# Sheet1.net
KiCad netlist of a schematic drawn in Altium Designer
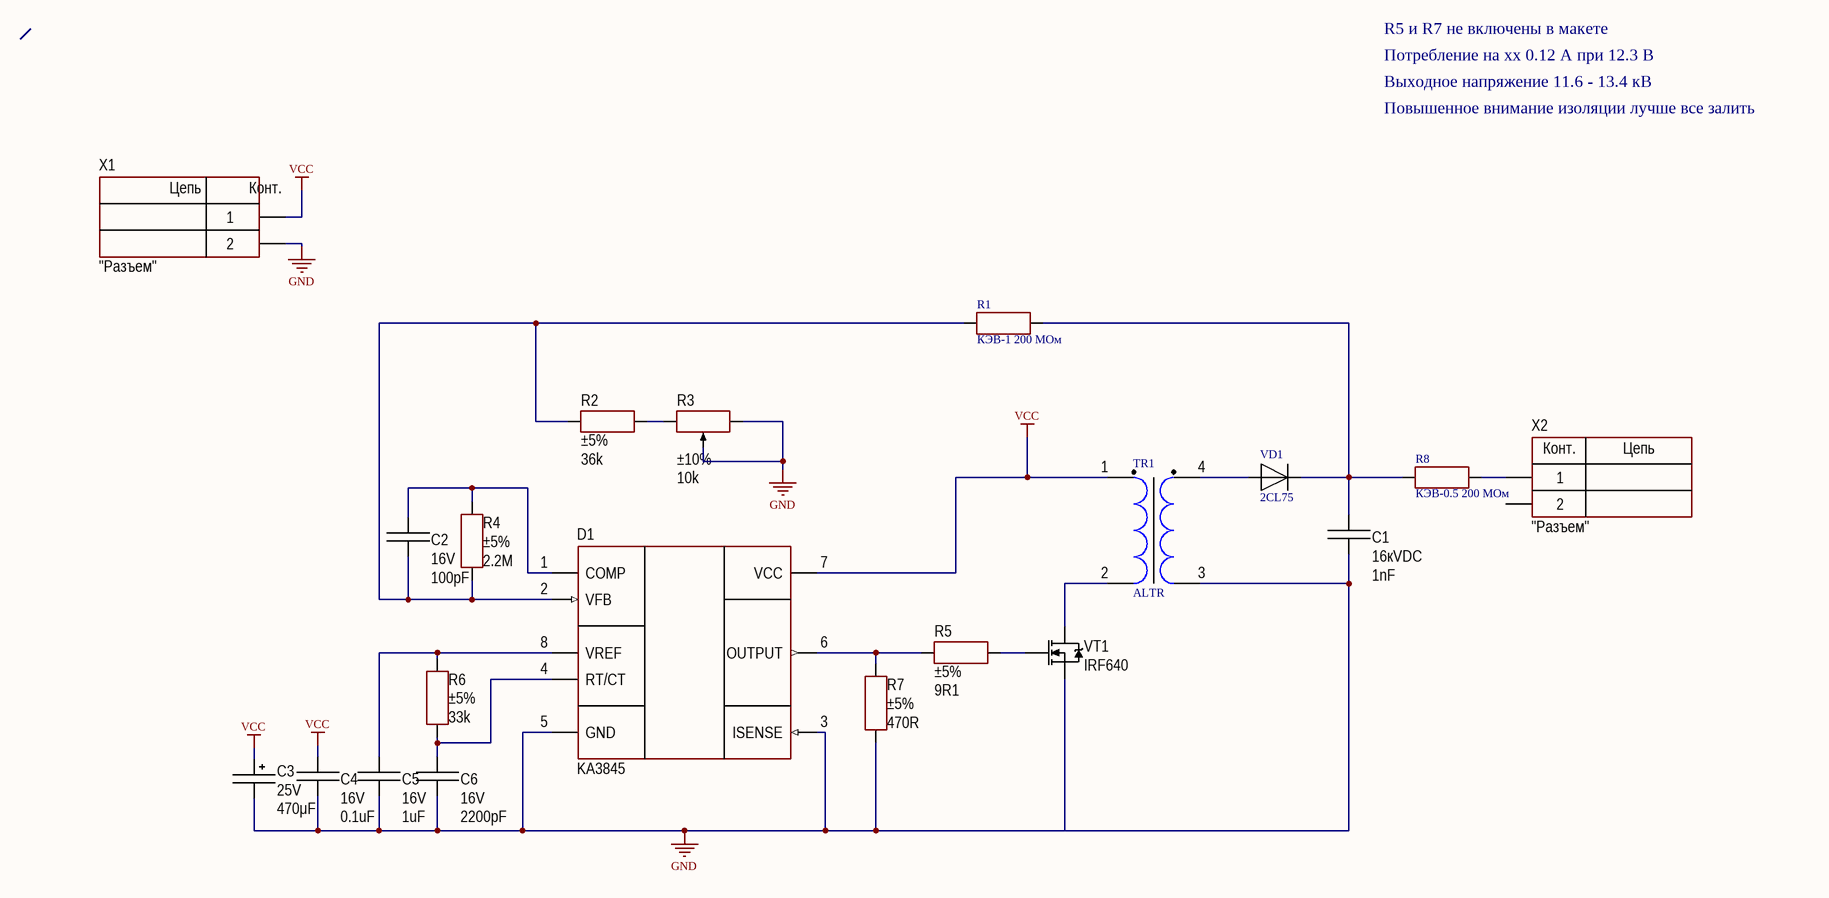
[diagram p0: Sheet1.SchDoc]

(export (version "E")
  (design (tool "Eeschema 10.0.6"))
  (components
    (comp (ref "C1")
      (value "1nF")
      (footprint "HV CAP")
      (fields
        (field (name "MANUFACTURER") "Epcos")
        (field (name "PARTNUMBER") "B32774D4106K000")
        (field (name "VALUEMANUFACTURERPARTNUMBER") "Film capacitor, 1nF, 16кVDC, ±10%, 10.9mOhm, 31.5x15 mm, -40...+105°C")
        (field (name "VOLTAGE") "16кVDC")
      )
      (libsource (lib "capacitor") (part "Film"))
    )
    (comp (ref "C2")
      (value "100pF")
      (footprint "CAP: 0805")
      (fields
        (field (name "MANUFACTURER") "Yageo")
        (field (name "PARTNUMBER") "CC0805KRX7R7BB104")
        (field (name "VALUEMANUFACTURERPARTNUMBER") "Ceramic capacitor, 100pF, X7R, ±10%, 16V, 0805, -55...+125°C")
        (field (name "VOLTAGE") "16V")
      )
      (libsource (lib "capacitor") (part "Ceramic_0805"))
    )
    (comp (ref "C3")
      (value "470μF")
      (footprint "CAP: D10C5H12.5")
      (fields
        (field (name "MANUFACTURER") "Wurth")
        (field (name "PARTNUMBER") "860080475013")
        (field (name "VALUEMANUFACTURERPARTNUMBER") "Aluminium capacitor, 470μF, 25V, ±20%, 54mOhm, 14x10x5 mm, -55...+105°C")
        (field (name "VOLTAGE") "25V")
      )
      (libsource (lib "capacitor") (part "Aluminium"))
    )
    (comp (ref "C4")
      (value "0.1uF")
      (footprint "CAP: 0805")
      (fields
        (field (name "MANUFACTURER") "Yageo")
        (field (name "PARTNUMBER") "CC0805KRX7R7BB104")
        (field (name "VALUEMANUFACTURERPARTNUMBER") "Ceramic capacitor, 0.1uF, X7R, ±10%, 16V, 0805, -55...+125°C")
        (field (name "VOLTAGE") "16V")
      )
      (libsource (lib "capacitor") (part "Ceramic_0805"))
    )
    (comp (ref "C5")
      (value "1uF")
      (footprint "CAP: 0805")
      (fields
        (field (name "MANUFACTURER") "Yageo")
        (field (name "PARTNUMBER") "CC0805KRX7R7BB104")
        (field (name "VALUEMANUFACTURERPARTNUMBER") "Ceramic capacitor, 1uF, X7R, ±10%, 16V, 0805, -55...+125°C")
        (field (name "VOLTAGE") "16V")
      )
      (libsource (lib "capacitor") (part "Ceramic_0805"))
    )
    (comp (ref "C6")
      (value "2200pF")
      (footprint "CAP: 0805")
      (fields
        (field (name "MANUFACTURER") "Yageo")
        (field (name "PARTNUMBER") "CC0805KRX7R7BB104")
        (field (name "VALUEMANUFACTURERPARTNUMBER") "Ceramic capacitor, 2200pF, X7R, ±10%, 16V, 0805, -55...+125°C")
        (field (name "VOLTAGE") "16V")
      )
      (libsource (lib "capacitor") (part "Ceramic_0805"))
    )
    (comp (ref "D1")
      (value "~")
      (footprint "8-SOIC")
      (description "PWM controller")
      (fields
        (field (name "MANUFACTURER") "ON Semiconductor")
        (field (name "VALUEMANUFACTURERPARTNUMBER") "PWM controller, supply 10...30V, 500kHz, External switch, -40...+105°C, 8-SOIC")
        (field (name "PARTNUMBER") "KA3845")
      )
      (libsource (lib "ic-power-supply") (part "UC3842BVD1R2G"))
    )
    (comp (ref "R1")
      (value "КЭВ-1 200 МОм")
      (footprint "КЭВ-1 case")
      (libsource (lib "resistor") (part "HV RESISTOR КЭВ-1"))
    )
    (comp (ref "R2")
      (value "36k")
      (footprint "RES: 0805")
      (fields
        (field (name "MANUFACTURER") "Yageo")
        (field (name "PARTNUMBER") "RC0805JR-07100RL")
        (field (name "VALUEMANUFACTURERPARTNUMBER") "Resistor film, 36k, ±5%, 0805, 0.125W, -55...+125°C")
        (field (name "TOLERANCE") "±5%")
      )
      (libsource (lib "") (part "Resistor_0805_1"))
    )
    (comp (ref "R3")
      (value "10k")
      (footprint "RES: 3362P")
      (fields
        (field (name "MANUFACTURER") "Bourns")
        (field (name "PARTNUMBER") "3296W-1-103LF")
        (field (name "VALUEMANUFACTURERPARTNUMBER") "Resistor film, 10k, ±10%, 3296W, 0.5W, -55...+125°C")
        (field (name "TOLERANCE") "±10%")
      )
      (libsource (lib "resistor") (part "Trimmer"))
    )
    (comp (ref "R4")
      (value "2.2M")
      (footprint "RES: 0805")
      (fields
        (field (name "MANUFACTURER") "Yageo")
        (field (name "PARTNUMBER") "RC0805JR-07100RL")
        (field (name "VALUEMANUFACTURERPARTNUMBER") "Resistor film, 2.2M, ±5%, 0805, 0.125W, -55...+125°C")
        (field (name "TOLERANCE") "±5%")
      )
      (libsource (lib "") (part "Resistor_0805_2"))
    )
    (comp (ref "R5")
      (value "9R1")
      (footprint "RES: 0805")
      (fields
        (field (name "MANUFACTURER") "Yageo")
        (field (name "PARTNUMBER") "RC0805JR-07100RL")
        (field (name "VALUEMANUFACTURERPARTNUMBER") "Resistor film, 9R1, ±5%, 0805, 0.125W, -55...+125°C")
        (field (name "TOLERANCE") "±5%")
      )
      (libsource (lib "") (part "Resistor_0805_1"))
    )
    (comp (ref "R6")
      (value "33k")
      (footprint "RES: 0805")
      (fields
        (field (name "MANUFACTURER") "Yageo")
        (field (name "PARTNUMBER") "RC0805JR-07100RL")
        (field (name "VALUEMANUFACTURERPARTNUMBER") "Resistor film, 33k, ±5%, 0805, 0.125W, -55...+125°C")
        (field (name "TOLERANCE") "±5%")
      )
      (libsource (lib "") (part "Resistor_0805_2"))
    )
    (comp (ref "R7")
      (value "470R")
      (footprint "RES: 0805")
      (fields
        (field (name "MANUFACTURER") "Yageo")
        (field (name "PARTNUMBER") "RC0805JR-07100RL")
        (field (name "VALUEMANUFACTURERPARTNUMBER") "Resistor film, 470R, ±5%, 0805, 0.125W, -55...+125°C")
        (field (name "TOLERANCE") "±5%")
      )
      (libsource (lib "resistor") (part "Resistor_0805"))
    )
    (comp (ref "R8")
      (value "КЭВ-0.5 200 МОм")
      (footprint "КЭВ-1 case")
      (libsource (lib "resistor") (part "HV RESISTOR КЭВ-1"))
    )
    (comp (ref "TR1") (value "ALTR") (footprint "ALTR") (libsource (lib "transformer") (part "ALTR")))
    (comp (ref "VD1") (value "2CL75") (footprint "2CL75 DO 3x12") (libsource (lib "diode") (part "2CL75")))
    (comp (ref "VT1")
      (value "~")
      (footprint "TO-220 HV")
      (fields
        (field (name "MANUFACTURER") "Infineon Technologies")
        (field (name "VALUEMANUFACTURERPARTNUMBER") "MOSFET N-channel transistor, 80V, 7A, 9.1nC, 2.5W, 34mOhm, 756pF, 8-TDSON, -55...+150°C")
        (field (name "PARTNUMBER") "IRF640")
      )
      (libsource (lib "transistor") (part "MOSFET_N_123"))
    )
    (comp (ref "X1")
      (value "~")
      (footprint "CON: KF301-5.0-2P")
      (fields
        (field (name "MANUFACTURER") "Degson")
        (field (name "VALUEMANUFACTURERPARTNUMBER") "Terminal connector, 2pin, 3.5mm, 300VAC, 10A")
        (field (name "PARTNUMBER") "DG350-3.5-02P-14")
        (field (name "COMMENTTEXT") "\"Разъем\"")
      )
      (libsource (lib "connector") (part "Connector_terminal_2pin"))
    )
    (comp (ref "X2")
      (value "~")
      (footprint "CON: KF301-5.0-2P")
      (fields
        (field (name "MANUFACTURER") "Degson")
        (field (name "VALUEMANUFACTURERPARTNUMBER") "Terminal connector, 2pin, 3.5mm, 300VAC, 10A")
        (field (name "PARTNUMBER") "DG350-3.5-02P-14")
        (field (name "COMMENTTEXT") "\"Разъем\"")
      )
      (libsource (lib "") (part "Connector_terminal_2pin_1"))
    )
  )
  (nets
    (net (code "1") (name "GND") (class "Default")
      (node (ref "C1") (pin "2") (pinfunction "2_2") (pintype "passive"))
      (node (ref "C3") (pin "2") (pinfunction "2_2") (pintype "passive"))
      (node (ref "C4") (pin "1") (pinfunction "1_1") (pintype "passive"))
      (node (ref "C5") (pin "1") (pinfunction "1_1") (pintype "passive"))
      (node (ref "C6") (pin "1") (pinfunction "1_1") (pintype "passive"))
      (node (ref "D1") (pin "3") (pinfunction "ISENSE_3") (pintype "input"))
      (node (ref "D1") (pin "5") (pinfunction "GND_5") (pintype "passive"))
      (node (ref "R3") (pin "1") (pinfunction "1_1") (pintype "passive"))
      (node (ref "R3") (pin "2") (pinfunction "2_2") (pintype "passive"))
      (node (ref "R7") (pin "2") (pinfunction "2_2") (pintype "passive"))
      (node (ref "TR1") (pin "3") (pinfunction "3_3") (pintype "power_in"))
      (node (ref "VT1") (pin "3") (pinfunction "S_3") (pintype "passive"))
      (node (ref "X1") (pin "2") (pinfunction "2_2") (pintype "passive"))
    )
    (net (code "2") (name "Net-(C1-Pad1)") (class "Default")
      (node (ref "C1") (pin "1") (pinfunction "1_1") (pintype "passive"))
      (node (ref "R1") (pin "2") (pinfunction "2_2") (pintype "passive"))
      (node (ref "R8") (pin "1") (pinfunction "1_1") (pintype "passive"))
      (node (ref "VD1") (pin "2") (pinfunction "2_2") (pintype "passive"))
    )
    (net (code "3") (name "Net-(D1-COMP)") (class "Default")
      (node (ref "C2") (pin "2") (pinfunction "2_2") (pintype "passive"))
      (node (ref "D1") (pin "1") (pinfunction "COMP_1") (pintype "passive"))
      (node (ref "R4") (pin "2") (pinfunction "2_2") (pintype "passive"))
    )
    (net (code "4") (name "Net-(D1-OUTPUT)") (class "Default")
      (node (ref "D1") (pin "6") (pinfunction "OUTPUT_6") (pintype "output"))
      (node (ref "R5") (pin "2") (pinfunction "2_2") (pintype "passive"))
      (node (ref "R7") (pin "1") (pinfunction "1_1") (pintype "passive"))
    )
    (net (code "5") (name "Net-(D1-RT{slash}CT)") (class "Default")
      (node (ref "C6") (pin "2") (pinfunction "2_2") (pintype "passive"))
      (node (ref "D1") (pin "4") (pinfunction "RT/CT_4") (pintype "passive"))
      (node (ref "R6") (pin "1") (pinfunction "1_1") (pintype "passive"))
    )
    (net (code "6") (name "Net-(D1-VFB)") (class "Default")
      (node (ref "C2") (pin "1") (pinfunction "1_1") (pintype "passive"))
      (node (ref "D1") (pin "2") (pinfunction "VFB_2") (pintype "input"))
      (node (ref "R1") (pin "1") (pinfunction "1_1") (pintype "passive"))
      (node (ref "R2") (pin "2") (pinfunction "2_2") (pintype "passive"))
      (node (ref "R4") (pin "1") (pinfunction "1_1") (pintype "passive"))
    )
    (net (code "7") (name "Net-(D1-VREF)") (class "Default")
      (node (ref "C5") (pin "2") (pinfunction "2_2") (pintype "passive"))
      (node (ref "D1") (pin "8") (pinfunction "VREF_8") (pintype "passive"))
      (node (ref "R6") (pin "2") (pinfunction "2_2") (pintype "passive"))
    )
    (net (code "8") (name "Net-(R2-Pad1)") (class "Default")
      (node (ref "R2") (pin "1") (pinfunction "1_1") (pintype "passive"))
      (node (ref "R3") (pin "3") (pinfunction "3_3") (pintype "passive"))
    )
    (net (code "9") (name "Net-(R8-Pad2)") (class "Default")
      (node (ref "R8") (pin "2") (pinfunction "2_2") (pintype "passive"))
      (node (ref "X2") (pin "1") (pinfunction "1_1") (pintype "passive"))
    )
    (net (code "10") (name "Net-(TR1-Pad4)") (class "Default")
      (node (ref "TR1") (pin "4") (pinfunction "4_4") (pintype "power_in"))
      (node (ref "VD1") (pin "1") (pinfunction "1_1") (pintype "passive"))
    )
    (net (code "11") (name "Net-(VT1-D)") (class "Default")
      (node (ref "TR1") (pin "2") (pinfunction "2_2") (pintype "power_in"))
      (node (ref "VT1") (pin "2") (pinfunction "D_2") (pintype "passive"))
    )
    (net (code "12") (name "Net-(VT1-G)") (class "Default")
      (node (ref "R5") (pin "1") (pinfunction "1_1") (pintype "passive"))
      (node (ref "VT1") (pin "1") (pinfunction "G_1") (pintype "passive"))
    )
    (net (code "13") (name "VCC") (class "Default")
      (node (ref "C3") (pin "1") (pinfunction "1_1") (pintype "passive"))
      (node (ref "C4") (pin "2") (pinfunction "2_2") (pintype "passive"))
      (node (ref "D1") (pin "7") (pinfunction "VCC_7") (pintype "passive"))
      (node (ref "TR1") (pin "1") (pinfunction "1_1") (pintype "power_in"))
      (node (ref "X1") (pin "1") (pinfunction "1_1") (pintype "passive"))
    )
    (net (code "14") (name "unconnected-(X2-Pad2)") (class "Default")
      (node (ref "X2") (pin "2") (pinfunction "2_2") (pintype "passive"))
    )
  )
)
